# botom_batery.net
KiCad netlist of a schematic drawn in EAGLE
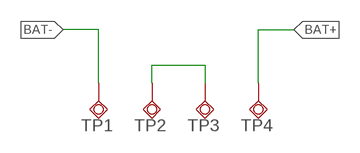
[diagram p0: schematic, sheet 1]

(export (version "E")
  (design (tool "Eeschema 10.0.6"))
  (components
    (comp (ref "TP1")
      (value "TPSQB1,27")
      (footprint "eagle-import:B1,27")
      (libsource (lib "eagle-import") (part "TPSQB1,27"))
    )
    (comp (ref "TP2")
      (value "TPSQB1,27")
      (footprint "eagle-import:B1,27")
      (libsource (lib "eagle-import") (part "TPSQB1,27"))
    )
    (comp (ref "TP3")
      (value "TPSQB1,27")
      (footprint "eagle-import:B1,27")
      (libsource (lib "eagle-import") (part "TPSQB1,27"))
    )
    (comp (ref "TP4")
      (value "TPSQB1,27")
      (footprint "eagle-import:B1,27")
      (libsource (lib "eagle-import") (part "TPSQB1,27"))
    )
  )
  (nets
    (net (code "1") (name "BAT+") (class "Default")
      (node (ref "TP4") (pin "TP") (pinfunction "TP_TP") (pintype "input"))
    )
    (net (code "2") (name "BAT-") (class "Default")
      (node (ref "TP1") (pin "TP") (pinfunction "TP_TP") (pintype "input"))
    )
    (net (code "3") (name "Net-(TP2-PadTP)") (class "Default")
      (node (ref "TP2") (pin "TP") (pinfunction "TP_TP") (pintype "input"))
      (node (ref "TP3") (pin "TP") (pinfunction "TP_TP") (pintype "input"))
    )
  )
)
